# pwmBoard.net
KiCad netlist of a schematic drawn in EAGLE
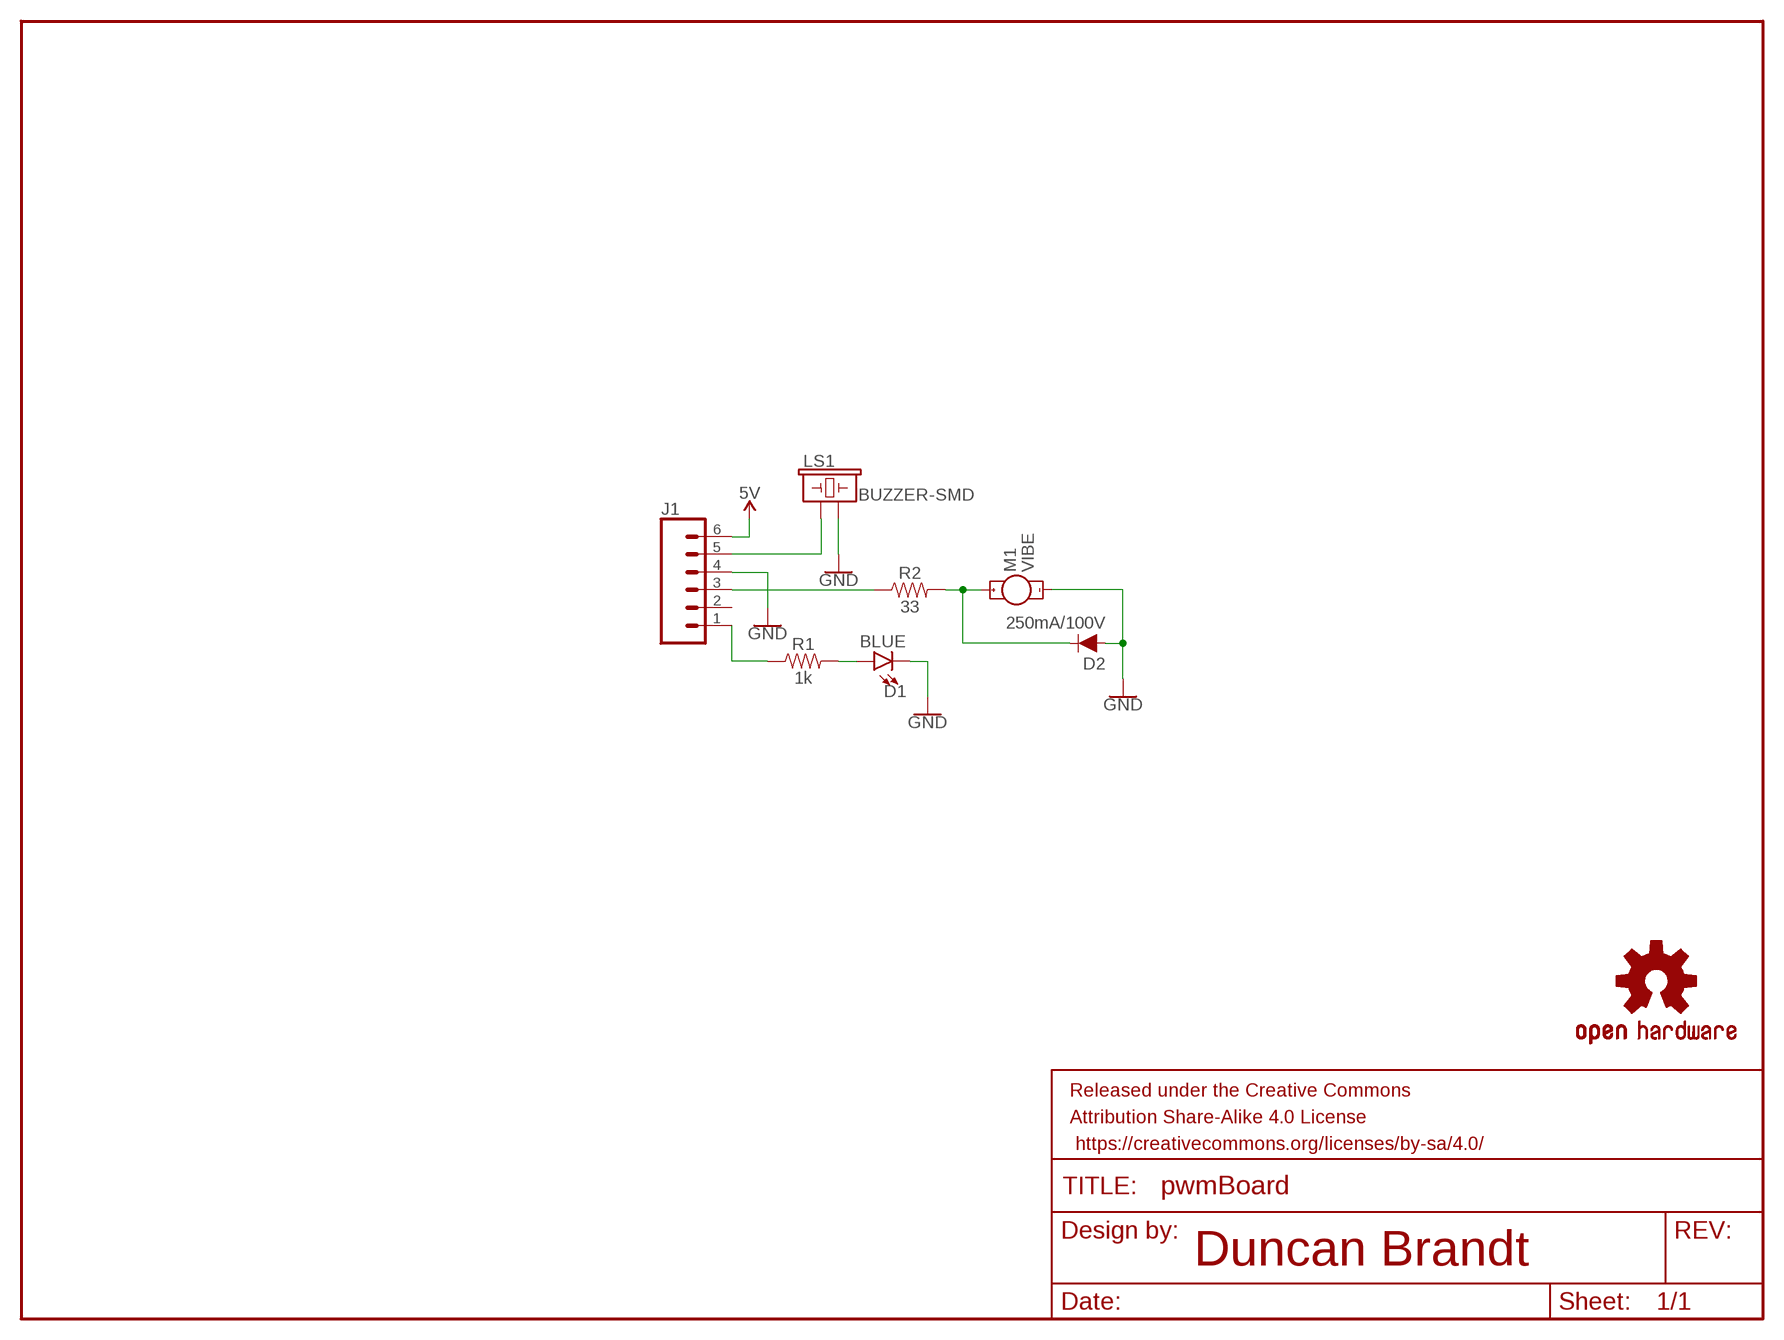
[diagram p0: schematic, sheet 1]

(export (version "E")
  (design (tool "Eeschema 10.0.6"))
  (components
    (comp (ref "D1")
      (value "BLUE")
      (footprint "eagle-import:LED-1206")
      (libsource (lib "eagle-import") (part "LED-BLUE1206"))
    )
    (comp (ref "D2")
      (value "250mA/100V")
      (footprint "eagle-import:SOD-323")
      (libsource (lib "eagle-import") (part "DIODE-BAS16J"))
    )
    (comp (ref "FRAME1")
      (value "FRAME-LETTER")
      (footprint "eagle-import:CREATIVE_COMMONS")
      (libsource (lib "eagle-import") (part "FRAME-LETTER"))
    )
    (comp (ref "J1")
      (value "CONN_06SILK_FEMALE_PTH")
      (footprint "eagle-import:1X06")
      (libsource (lib "eagle-import") (part "CONN_06SILK_FEMALE_PTH"))
    )
    (comp (ref "LOGO1")
      (value "OSHW-LOGOL")
      (footprint "eagle-import:OSHW-LOGO-L")
      (libsource (lib "eagle-import") (part "OSHW-LOGOL"))
    )
    (comp (ref "LS1")
      (value "BUZZER-SMD")
      (footprint "eagle-import:BUZZER-CCV")
      (libsource (lib "eagle-import") (part "BUZZER-SMD"))
    )
    (comp (ref "M1")
      (value "VIBE")
      (footprint "eagle-import:VIBE-MOTOR-10MM")
      (libsource (lib "eagle-import") (part "MOTOR10MM"))
    )
    (comp (ref "R1")
      (value "1k")
      (footprint "eagle-import:0603")
      (libsource (lib "eagle-import") (part "1KOHM-0603-1/10W-1%"))
    )
    (comp (ref "R2")
      (value "33")
      (footprint "eagle-import:0603")
      (libsource (lib "eagle-import") (part "33OHM-0603-1/10W-1%"))
    )
  )
  (nets
    (net (code "1") (name "5V") (class "Default")
      (node (ref "J1") (pin "6") (pinfunction "6_6") (pintype "passive"))
    )
    (net (code "2") (name "GND") (class "Default")
      (node (ref "D1") (pin "C") (pinfunction "C_C") (pintype "passive"))
      (node (ref "D2") (pin "A") (pinfunction "A_A") (pintype "passive"))
      (node (ref "J1") (pin "4") (pinfunction "4_4") (pintype "passive"))
      (node (ref "LS1") (pin "-") (pinfunction "2_-") (pintype "passive"))
      (node (ref "M1") (pin "-") (pinfunction "-_-") (pintype "bidirectional"))
    )
    (net (code "3") (name "Net-(D1-PadA)") (class "Default")
      (node (ref "D1") (pin "A") (pinfunction "A_A") (pintype "passive"))
      (node (ref "R1") (pin "2") (pinfunction "2_2") (pintype "passive"))
    )
    (net (code "4") (name "Net-(D2-PadC)") (class "Default")
      (node (ref "D2") (pin "C") (pinfunction "C_C") (pintype "passive"))
      (node (ref "M1") (pin "+") (pinfunction "+_+") (pintype "bidirectional"))
      (node (ref "R2") (pin "2") (pinfunction "2_2") (pintype "passive"))
    )
    (net (code "5") (name "Net-(J1-Pad1)") (class "Default")
      (node (ref "J1") (pin "1") (pinfunction "1_1") (pintype "passive"))
      (node (ref "R1") (pin "1") (pinfunction "1_1") (pintype "passive"))
    )
    (net (code "6") (name "Net-(J1-Pad3)") (class "Default")
      (node (ref "J1") (pin "3") (pinfunction "3_3") (pintype "passive"))
      (node (ref "R2") (pin "1") (pinfunction "1_1") (pintype "passive"))
    )
    (net (code "7") (name "Net-(LS1-1)") (class "Default")
      (node (ref "J1") (pin "5") (pinfunction "5_5") (pintype "passive"))
      (node (ref "LS1") (pin "+") (pinfunction "1_+") (pintype "passive"))
    )
    (net (code "8") (name "unconnected-(J1-Pad2)") (class "Default")
      (node (ref "J1") (pin "2") (pinfunction "2_2") (pintype "passive"))
    )
  )
)
